# Gecko_IO.net
KiCad netlist of a schematic drawn in Altium Designer
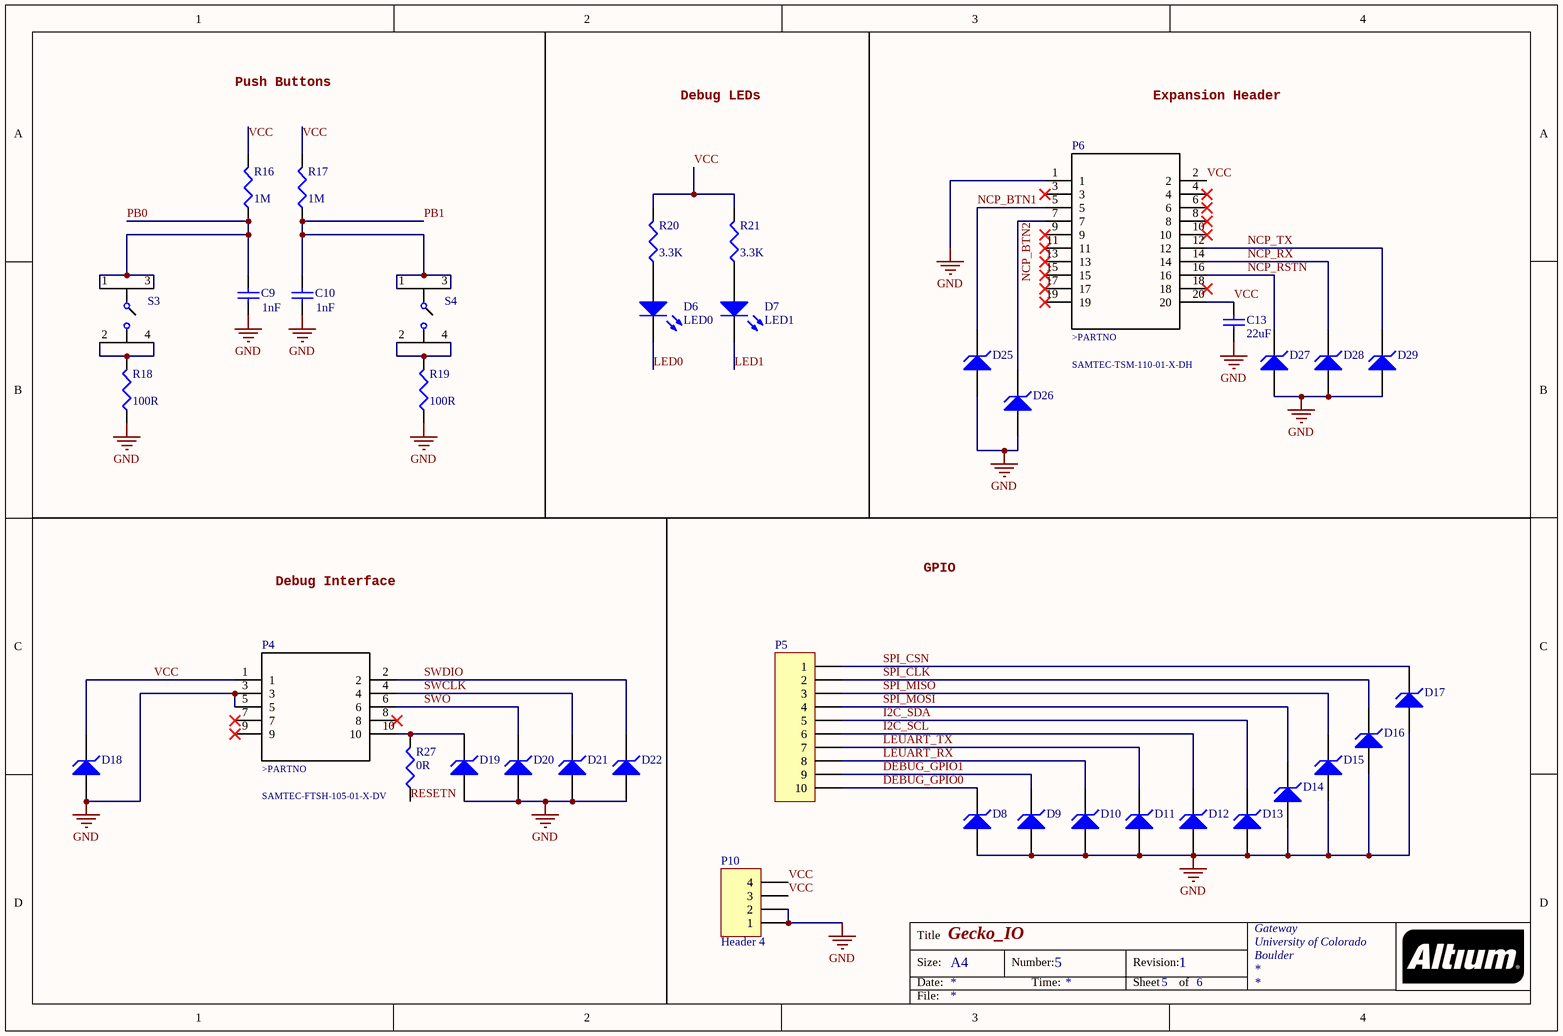
[diagram p0: Gecko_IO.SchDoc]

(export (version "E")
  (design (tool "Eeschema 10.0.6"))
  (components
    (comp (ref "C9")
      (value "1nF")
      (footprint "1608[0603]")
      (description "CAP CER 1000PF 50V X7R 0603")
      (fields
        (field (name "DIGI-KEY PART NUMBER") "478-5006-1-ND")
        (field (name "MANUFACTURER") "AVX Corporation")
        (field (name "PUBLISHER") "Altium Limited")
      )
      (libsource (lib "Miscellaneous Devices") (part "Cap"))
    )
    (comp (ref "C10")
      (value "1nF")
      (footprint "1608[0603]")
      (description "CAP CER 1000PF 50V X7R 0603")
      (fields
        (field (name "DIGI-KEY PART NUMBER") "478-5006-1-ND")
        (field (name "MANUFACTURER") "AVX Corporation")
        (field (name "PUBLISHER") "Altium Limited")
      )
      (libsource (lib "Miscellaneous Devices") (part "Cap"))
    )
    (comp (ref "C13")
      (value "22uF")
      (footprint "1608[0603]")
      (description "CAP CER 22UF 10V X5R 0603")
      (fields
        (field (name "MANUFACTURER") "Samsung Electro-Mechanics")
        (field (name "MANUFACTURER PART NUMBER") "CL10A226MPCNUBE")
        (field (name "PUBLISHER") "Altium Limited")
      )
      (libsource (lib "Miscellaneous Devices") (part "Cap"))
    )
    (comp (ref "D6")
      (value "LED0")
      (footprint "1608[0603]")
      (description "LED GREEN DIFFUSED 0603 SMD")
      (fields
        (field (name "DIGI-KEY PART NUMBER") "475-3118-1-ND")
        (field (name "MANUFACTURER") "OSRAM Opto Semiconductors Inc.")
      )
      (libsource (lib "Miscellaneous Devices") (part "LED2"))
    )
    (comp (ref "D7")
      (value "LED1")
      (footprint "1608[0603]")
      (description "LED GREEN DIFFUSED 0603 SMD")
      (fields
        (field (name "DIGI-KEY PART NUMBER") "475-3118-1-ND")
        (field (name "MANUFACTURER") "OSRAM Opto Semiconductors Inc.")
      )
      (libsource (lib "Miscellaneous Devices") (part "LED2"))
    )
    (comp (ref "D8")
      (value "CZRQR3V3B-HF")
      (footprint "0402")
      (description "DIODE ZENER 3.3V 125MW 0402")
      (fields
        (field (name "DIGI-KEY PART NUMBER") "641-1682-1-ND")
        (field (name "MANUFACTURER") "Comchip Technology")
      )
      (libsource (lib "Miscellaneous Devices") (part "D Zener"))
    )
    (comp (ref "D9")
      (value "CZRQR3V3B-HF")
      (footprint "0402")
      (description "DIODE ZENER 3.3V 125MW 0402")
      (fields
        (field (name "DIGI-KEY PART NUMBER") "641-1682-1-ND")
        (field (name "MANUFACTURER") "Comchip Technology")
      )
      (libsource (lib "Miscellaneous Devices") (part "D Zener"))
    )
    (comp (ref "D10")
      (value "CZRQR3V3B-HF")
      (footprint "0402")
      (description "DIODE ZENER 3.3V 125MW 0402")
      (fields
        (field (name "DIGI-KEY PART NUMBER") "641-1682-1-ND")
        (field (name "MANUFACTURER") "Comchip Technology")
      )
      (libsource (lib "Miscellaneous Devices") (part "D Zener"))
    )
    (comp (ref "D11")
      (value "CZRQR3V3B-HF")
      (footprint "0402")
      (description "DIODE ZENER 3.3V 125MW 0402")
      (fields
        (field (name "DIGI-KEY PART NUMBER") "641-1682-1-ND")
        (field (name "MANUFACTURER") "Comchip Technology")
      )
      (libsource (lib "Miscellaneous Devices") (part "D Zener"))
    )
    (comp (ref "D12")
      (value "CZRQR3V3B-HF")
      (footprint "0402")
      (description "DIODE ZENER 3.3V 125MW 0402")
      (fields
        (field (name "DIGI-KEY PART NUMBER") "641-1682-1-ND")
        (field (name "MANUFACTURER") "Comchip Technology")
      )
      (libsource (lib "Miscellaneous Devices") (part "D Zener"))
    )
    (comp (ref "D13")
      (value "CZRQR3V3B-HF")
      (footprint "0402")
      (description "DIODE ZENER 3.3V 125MW 0402")
      (fields
        (field (name "DIGI-KEY PART NUMBER") "641-1682-1-ND")
        (field (name "MANUFACTURER") "Comchip Technology")
      )
      (libsource (lib "Miscellaneous Devices") (part "D Zener"))
    )
    (comp (ref "D14")
      (value "CZRQR3V3B-HF")
      (footprint "0402")
      (description "DIODE ZENER 3.3V 125MW 0402")
      (fields
        (field (name "DIGI-KEY PART NUMBER") "641-1682-1-ND")
        (field (name "MANUFACTURER") "Comchip Technology")
      )
      (libsource (lib "Miscellaneous Devices") (part "D Zener"))
    )
    (comp (ref "D15")
      (value "CZRQR3V3B-HF")
      (footprint "0402")
      (description "DIODE ZENER 3.3V 125MW 0402")
      (fields
        (field (name "DIGI-KEY PART NUMBER") "641-1682-1-ND")
        (field (name "MANUFACTURER") "Comchip Technology")
      )
      (libsource (lib "Miscellaneous Devices") (part "D Zener"))
    )
    (comp (ref "D16")
      (value "CZRQR3V3B-HF")
      (footprint "0402")
      (description "DIODE ZENER 3.3V 125MW 0402")
      (fields
        (field (name "DIGI-KEY PART NUMBER") "641-1682-1-ND")
        (field (name "MANUFACTURER") "Comchip Technology")
      )
      (libsource (lib "Miscellaneous Devices") (part "D Zener"))
    )
    (comp (ref "D17")
      (value "CZRQR3V3B-HF")
      (footprint "0402")
      (description "DIODE ZENER 3.3V 125MW 0402")
      (fields
        (field (name "DIGI-KEY PART NUMBER") "641-1682-1-ND")
        (field (name "MANUFACTURER") "Comchip Technology")
      )
      (libsource (lib "Miscellaneous Devices") (part "D Zener"))
    )
    (comp (ref "D18")
      (value "CZRQR3V3B-HF")
      (footprint "0402")
      (description "DIODE ZENER 3.3V 125MW 0402")
      (fields
        (field (name "DIGI-KEY PART NUMBER") "641-1682-1-ND")
        (field (name "MANUFACTURER") "Comchip Technology")
      )
      (libsource (lib "Miscellaneous Devices") (part "D Zener"))
    )
    (comp (ref "D19")
      (value "CZRQR3V3B-HF")
      (footprint "0402")
      (description "DIODE ZENER 3.3V 125MW 0402")
      (fields
        (field (name "DIGI-KEY PART NUMBER") "641-1682-1-ND")
        (field (name "MANUFACTURER") "Comchip Technology")
      )
      (libsource (lib "Miscellaneous Devices") (part "D Zener"))
    )
    (comp (ref "D20")
      (value "CZRQR3V3B-HF")
      (footprint "0402")
      (description "DIODE ZENER 3.3V 125MW 0402")
      (fields
        (field (name "DIGI-KEY PART NUMBER") "641-1682-1-ND")
        (field (name "MANUFACTURER") "Comchip Technology")
      )
      (libsource (lib "Miscellaneous Devices") (part "D Zener"))
    )
    (comp (ref "D21")
      (value "CZRQR3V3B-HF")
      (footprint "0402")
      (description "DIODE ZENER 3.3V 125MW 0402")
      (fields
        (field (name "DIGI-KEY PART NUMBER") "641-1682-1-ND")
        (field (name "MANUFACTURER") "Comchip Technology")
      )
      (libsource (lib "Miscellaneous Devices") (part "D Zener"))
    )
    (comp (ref "D22")
      (value "CZRQR3V3B-HF")
      (footprint "0402")
      (description "DIODE ZENER 3.3V 125MW 0402")
      (fields
        (field (name "DIGI-KEY PART NUMBER") "641-1682-1-ND")
        (field (name "MANUFACTURER") "Comchip Technology")
      )
      (libsource (lib "Miscellaneous Devices") (part "D Zener"))
    )
    (comp (ref "D25")
      (value "CZRQR3V3B-HF")
      (footprint "0402")
      (description "DIODE ZENER 3.3V 125MW 0402")
      (fields
        (field (name "DIGI-KEY PART NUMBER") "641-1682-1-ND")
        (field (name "MANUFACTURER") "Comchip Technology")
      )
      (libsource (lib "Miscellaneous Devices") (part "D Zener"))
    )
    (comp (ref "D26")
      (value "CZRQR3V3B-HF")
      (footprint "0402")
      (description "DIODE ZENER 3.3V 125MW 0402")
      (fields
        (field (name "DIGI-KEY PART NUMBER") "641-1682-1-ND")
        (field (name "MANUFACTURER") "Comchip Technology")
      )
      (libsource (lib "Miscellaneous Devices") (part "D Zener"))
    )
    (comp (ref "D27")
      (value "CZRQR3V3B-HF")
      (footprint "0402")
      (description "DIODE ZENER 3.3V 125MW 0402")
      (fields
        (field (name "DIGI-KEY PART NUMBER") "641-1682-1-ND")
        (field (name "MANUFACTURER") "Comchip Technology")
      )
      (libsource (lib "Miscellaneous Devices") (part "D Zener"))
    )
    (comp (ref "D28")
      (value "CZRQR3V3B-HF")
      (footprint "0402")
      (description "DIODE ZENER 3.3V 125MW 0402")
      (fields
        (field (name "DIGI-KEY PART NUMBER") "641-1682-1-ND")
        (field (name "MANUFACTURER") "Comchip Technology")
      )
      (libsource (lib "Miscellaneous Devices") (part "D Zener"))
    )
    (comp (ref "D29")
      (value "CZRQR3V3B-HF")
      (footprint "0402")
      (description "DIODE ZENER 3.3V 125MW 0402")
      (fields
        (field (name "DIGI-KEY PART NUMBER") "641-1682-1-ND")
        (field (name "MANUFACTURER") "Comchip Technology")
      )
      (libsource (lib "Miscellaneous Devices") (part "D Zener"))
    )
    (comp (ref "P4")
      (value "PROG_HDR")
      (footprint "SAMTEC-FTSH-105-01-X-DV")
      (description ".050\" X .050 TERMINAL STRIP")
      (fields
        (field (name "MANUFACTURER") "Samtec")
        (field (name "MANUFACTURER PART NUMBER") "FTSH-105-01-F-DV-K-TR")
      )
      (libsource (lib "Debug_connector") (part "SAMTEC-FTSH-105-01-X-DV"))
    )
    (comp (ref "P5")
      (value "~")
      (footprint "HDR1X10")
      (description "Header, 10-Pin")
      (fields (field (name "PUBLISHER") "Altium Limited"))
      (libsource (lib "Miscellaneous Connectors") (part "Header 10"))
    )
    (comp (ref "P6")
      (value "TSM-110-01-L-DH-A-P-TR")
      (footprint "SAMTEC-TSM-110-01-X-DH")
      (description ".025 SQ. TERMINAL STRIPS")
      (fields
        (field (name "DIGI-KEY PART NUMBER") "SAM14883CT-ND")
        (field (name "MANUFACTURER") "Samtec Inc.")
      )
      (libsource (lib "SAMTEC-TSM-110-01-X-DH") (part "SAMTEC-TSM-110-01-X-DH"))
    )
    (comp (ref "P10")
      (value "Header 4")
      (footprint "HDR1X4")
      (description "Header, 4-Pin")
      (fields (field (name "PUBLISHER") "Altium Limited"))
      (libsource (lib "Miscellaneous Connectors") (part "Header 4"))
    )
    (comp (ref "R16")
      (value "1M")
      (footprint "1608[0603]")
      (description "RES SMD 1M OHM 5% 1/10W 0603")
      (fields
        (field (name "DIGI-KEY PART NUMBER") "1276-5134-1-ND")
        (field (name "MANUFACTURER") "Samsung Electro-Mechanics")
        (field (name "PUBLISHER") "Altium Limited")
      )
      (libsource (lib "Miscellaneous Devices") (part "Res3"))
    )
    (comp (ref "R17")
      (value "1M")
      (footprint "1608[0603]")
      (description "RES SMD 1M OHM 5% 1/10W 0603")
      (fields
        (field (name "DIGI-KEY PART NUMBER") "1276-5134-1-ND")
        (field (name "MANUFACTURER") "Samsung Electro-Mechanics")
        (field (name "PUBLISHER") "Altium Limited")
      )
      (libsource (lib "Miscellaneous Devices") (part "Res3"))
    )
    (comp (ref "R18")
      (value "100R")
      (footprint "1608[0603]")
      (description "RES SMD 100 OHM 5% 1/10W 0603")
      (fields
        (field (name "DIGI-KEY PART NUMBER") "541-4059-1-ND")
        (field (name "MANUFACTURER") "Vishay Dale")
        (field (name "PUBLISHER") "Altium Limited")
      )
      (libsource (lib "Miscellaneous Devices") (part "Res3"))
    )
    (comp (ref "R19")
      (value "100R")
      (footprint "1608[0603]")
      (description "RES SMD 100 OHM 5% 1/10W 0603")
      (fields
        (field (name "DIGI-KEY PART NUMBER") "541-4059-1-ND")
        (field (name "MANUFACTURER") "Vishay Dale")
        (field (name "PUBLISHER") "Altium Limited")
      )
      (libsource (lib "Miscellaneous Devices") (part "Res3"))
    )
    (comp (ref "R20")
      (value "3.3K")
      (footprint "1608[0603]")
      (description "RES SMD 3.3K OHM 5% 1/10W 0603")
      (fields
        (field (name "DIGI-KEY PART NUMBER") "P3.3KGCT-ND")
        (field (name "MANUFACTURER") "Panasonic Electronic Components")
      )
      (libsource (lib "Miscellaneous Devices") (part "Res3"))
    )
    (comp (ref "R21")
      (value "3.3K")
      (footprint "1608[0603]")
      (description "RES SMD 3.3K OHM 5% 1/10W 0603")
      (fields
        (field (name "DIGI-KEY PART NUMBER") "P3.3KGCT-ND")
        (field (name "MANUFACTURER") "Panasonic Electronic Components")
      )
      (libsource (lib "Miscellaneous Devices") (part "Res3"))
    )
    (comp (ref "R27")
      (value "0R")
      (footprint "C1206")
      (description "RES 0 OHM JUMPER 1/8W 0603")
      (fields
        (field (name "DIGI-KEY PART NUMBER") "749-1745-1-ND")
        (field (name "MANUFACTURER") "Vishay Beyschlag")
        (field (name "PUBLISHER") "Altium Limited")
      )
      (libsource (lib "Miscellaneous Devices") (part "Res3"))
    )
    (comp (ref "S3")
      (value "PB0")
      (footprint "430182043816")
      (description "SWITCH TACTILE SPST-NO 0.05A 12V")
      (fields
        (field (name "MANUFACTURER PART NUMBER") "430182043816")
        (field (name "MANUFACTURER") "Wurth Electronics")
      )
      (libsource (lib "430182043816") (part "430182043816"))
    )
    (comp (ref "S4")
      (value "PB1")
      (footprint "430182043816")
      (description "SWITCH TACTILE SPST-NO 0.05A 12V")
      (fields
        (field (name "MANUFACTURER PART NUMBER") "430182043816")
        (field (name "MANUFACTURER") "Wurth Electronics")
      )
      (libsource (lib "430182043816") (part "430182043816"))
    )
  )
  (nets
    (net (code "1") (name "/DEBUG_GPIO0") (class "Default")
      (node (ref "D8") (pin "2") (pinfunction "K_2") (pintype "passive"))
      (node (ref "P5") (pin "10") (pinfunction "10_10") (pintype "passive"))
    )
    (net (code "2") (name "/DEBUG_GPIO1") (class "Default")
      (node (ref "D9") (pin "2") (pinfunction "K_2") (pintype "passive"))
      (node (ref "P5") (pin "9") (pinfunction "9_9") (pintype "passive"))
    )
    (net (code "3") (name "/I2C_SCL") (class "Default")
      (node (ref "D12") (pin "2") (pinfunction "K_2") (pintype "passive"))
      (node (ref "P5") (pin "6") (pinfunction "6_6") (pintype "passive"))
    )
    (net (code "4") (name "/I2C_SDA") (class "Default")
      (node (ref "D13") (pin "2") (pinfunction "K_2") (pintype "passive"))
      (node (ref "P5") (pin "5") (pinfunction "5_5") (pintype "passive"))
    )
    (net (code "5") (name "/LED0") (class "Default")
      (node (ref "D6") (pin "2") (pinfunction "K_2") (pintype "passive"))
    )
    (net (code "6") (name "/LED1") (class "Default")
      (node (ref "D7") (pin "2") (pinfunction "K_2") (pintype "passive"))
    )
    (net (code "7") (name "/LEUART_RX") (class "Default")
      (node (ref "D10") (pin "2") (pinfunction "K_2") (pintype "passive"))
      (node (ref "P5") (pin "8") (pinfunction "8_8") (pintype "passive"))
    )
    (net (code "8") (name "/LEUART_TX") (class "Default")
      (node (ref "D11") (pin "2") (pinfunction "K_2") (pintype "passive"))
      (node (ref "P5") (pin "7") (pinfunction "7_7") (pintype "passive"))
    )
    (net (code "9") (name "/NCP_BTN1") (class "Default")
      (node (ref "D25") (pin "2") (pinfunction "K_2") (pintype "passive"))
      (node (ref "P6") (pin "5") (pinfunction "5_5") (pintype "passive"))
    )
    (net (code "10") (name "/NCP_BTN2") (class "Default")
      (node (ref "D26") (pin "2") (pinfunction "K_2") (pintype "passive"))
      (node (ref "P6") (pin "7") (pinfunction "7_7") (pintype "passive"))
    )
    (net (code "11") (name "/NCP_RSTN") (class "Default")
      (node (ref "D27") (pin "2") (pinfunction "K_2") (pintype "passive"))
      (node (ref "P6") (pin "16") (pinfunction "16_16") (pintype "passive"))
    )
    (net (code "12") (name "/NCP_RX") (class "Default")
      (node (ref "D28") (pin "2") (pinfunction "K_2") (pintype "passive"))
      (node (ref "P6") (pin "14") (pinfunction "14_14") (pintype "passive"))
    )
    (net (code "13") (name "/NCP_TX") (class "Default")
      (node (ref "D29") (pin "2") (pinfunction "K_2") (pintype "passive"))
      (node (ref "P6") (pin "12") (pinfunction "12_12") (pintype "passive"))
    )
    (net (code "14") (name "/PB0") (class "Default")
      (node (ref "C9") (pin "2") (pinfunction "2_2") (pintype "passive"))
      (node (ref "R16") (pin "1") (pinfunction "1_1") (pintype "passive"))
      (node (ref "S3") (pin "1") (pinfunction "1_1") (pintype "passive"))
      (node (ref "S3") (pin "3") (pinfunction "3_3") (pintype "passive"))
    )
    (net (code "15") (name "/PB1") (class "Default")
      (node (ref "C10") (pin "2") (pinfunction "2_2") (pintype "passive"))
      (node (ref "R17") (pin "1") (pinfunction "1_1") (pintype "passive"))
      (node (ref "S4") (pin "1") (pinfunction "1_1") (pintype "passive"))
      (node (ref "S4") (pin "3") (pinfunction "3_3") (pintype "passive"))
    )
    (net (code "16") (name "/RESETN") (class "Default")
      (node (ref "R27") (pin "1") (pinfunction "1_1") (pintype "passive"))
    )
    (net (code "17") (name "/SPI_CLK") (class "Default")
      (node (ref "D16") (pin "2") (pinfunction "K_2") (pintype "passive"))
      (node (ref "P5") (pin "2") (pinfunction "2_2") (pintype "passive"))
    )
    (net (code "18") (name "/SPI_CSN") (class "Default")
      (node (ref "D17") (pin "2") (pinfunction "K_2") (pintype "passive"))
      (node (ref "P5") (pin "1") (pinfunction "1_1") (pintype "passive"))
    )
    (net (code "19") (name "/SPI_MISO") (class "Default")
      (node (ref "D15") (pin "2") (pinfunction "K_2") (pintype "passive"))
      (node (ref "P5") (pin "3") (pinfunction "3_3") (pintype "passive"))
    )
    (net (code "20") (name "/SPI_MOSI") (class "Default")
      (node (ref "D14") (pin "2") (pinfunction "K_2") (pintype "passive"))
      (node (ref "P5") (pin "4") (pinfunction "4_4") (pintype "passive"))
    )
    (net (code "21") (name "/SWCLK") (class "Default")
      (node (ref "D21") (pin "2") (pinfunction "K_2") (pintype "passive"))
      (node (ref "P4") (pin "4") (pinfunction "4_4") (pintype "passive"))
    )
    (net (code "22") (name "/SWDIO") (class "Default")
      (node (ref "D22") (pin "2") (pinfunction "K_2") (pintype "passive"))
      (node (ref "P4") (pin "2") (pinfunction "2_2") (pintype "passive"))
    )
    (net (code "23") (name "/SWO") (class "Default")
      (node (ref "D20") (pin "2") (pinfunction "K_2") (pintype "passive"))
      (node (ref "P4") (pin "6") (pinfunction "6_6") (pintype "passive"))
    )
    (net (code "24") (name "/VCC") (class "Default")
      (node (ref "C13") (pin "1") (pinfunction "1_1") (pintype "passive"))
      (node (ref "D18") (pin "2") (pinfunction "K_2") (pintype "passive"))
      (node (ref "P10") (pin "3") (pinfunction "3_3") (pintype "passive"))
      (node (ref "P10") (pin "4") (pinfunction "4_4") (pintype "passive"))
      (node (ref "P4") (pin "1") (pinfunction "1_1") (pintype "passive"))
      (node (ref "P6") (pin "2") (pinfunction "2_2") (pintype "passive"))
      (node (ref "P6") (pin "20") (pinfunction "20_20") (pintype "passive"))
      (node (ref "R16") (pin "2") (pinfunction "2_2") (pintype "passive"))
      (node (ref "R17") (pin "2") (pinfunction "2_2") (pintype "passive"))
      (node (ref "R20") (pin "2") (pinfunction "2_2") (pintype "passive"))
      (node (ref "R21") (pin "2") (pinfunction "2_2") (pintype "passive"))
    )
    (net (code "25") (name "GND") (class "Default")
      (node (ref "C10") (pin "1") (pinfunction "1_1") (pintype "passive"))
      (node (ref "C13") (pin "2") (pinfunction "2_2") (pintype "passive"))
      (node (ref "C9") (pin "1") (pinfunction "1_1") (pintype "passive"))
      (node (ref "D10") (pin "1") (pinfunction "A_1") (pintype "passive"))
      (node (ref "D11") (pin "1") (pinfunction "A_1") (pintype "passive"))
      (node (ref "D12") (pin "1") (pinfunction "A_1") (pintype "passive"))
      (node (ref "D13") (pin "1") (pinfunction "A_1") (pintype "passive"))
      (node (ref "D14") (pin "1") (pinfunction "A_1") (pintype "passive"))
      (node (ref "D15") (pin "1") (pinfunction "A_1") (pintype "passive"))
      (node (ref "D16") (pin "1") (pinfunction "A_1") (pintype "passive"))
      (node (ref "D17") (pin "1") (pinfunction "A_1") (pintype "passive"))
      (node (ref "D18") (pin "1") (pinfunction "A_1") (pintype "passive"))
      (node (ref "D19") (pin "1") (pinfunction "A_1") (pintype "passive"))
      (node (ref "D20") (pin "1") (pinfunction "A_1") (pintype "passive"))
      (node (ref "D21") (pin "1") (pinfunction "A_1") (pintype "passive"))
      (node (ref "D22") (pin "1") (pinfunction "A_1") (pintype "passive"))
      (node (ref "D25") (pin "1") (pinfunction "A_1") (pintype "passive"))
      (node (ref "D26") (pin "1") (pinfunction "A_1") (pintype "passive"))
      (node (ref "D27") (pin "1") (pinfunction "A_1") (pintype "passive"))
      (node (ref "D28") (pin "1") (pinfunction "A_1") (pintype "passive"))
      (node (ref "D29") (pin "1") (pinfunction "A_1") (pintype "passive"))
      (node (ref "D8") (pin "1") (pinfunction "A_1") (pintype "passive"))
      (node (ref "D9") (pin "1") (pinfunction "A_1") (pintype "passive"))
      (node (ref "P10") (pin "1") (pinfunction "1_1") (pintype "passive"))
      (node (ref "P10") (pin "2") (pinfunction "2_2") (pintype "passive"))
      (node (ref "P4") (pin "3") (pinfunction "3_3") (pintype "passive"))
      (node (ref "P4") (pin "5") (pinfunction "5_5") (pintype "passive"))
      (node (ref "P6") (pin "1") (pinfunction "1_1") (pintype "passive"))
      (node (ref "R18") (pin "1") (pinfunction "1_1") (pintype "passive"))
      (node (ref "R19") (pin "1") (pinfunction "1_1") (pintype "passive"))
    )
    (net (code "26") (name "Net-(D6-A)") (class "Default")
      (node (ref "D6") (pin "1") (pinfunction "A_1") (pintype "passive"))
      (node (ref "R20") (pin "1") (pinfunction "1_1") (pintype "passive"))
    )
    (net (code "27") (name "Net-(D7-A)") (class "Default")
      (node (ref "D7") (pin "1") (pinfunction "A_1") (pintype "passive"))
      (node (ref "R21") (pin "1") (pinfunction "1_1") (pintype "passive"))
    )
    (net (code "28") (name "Net-(D19-K)") (class "Default")
      (node (ref "D19") (pin "2") (pinfunction "K_2") (pintype "passive"))
      (node (ref "P4") (pin "10") (pinfunction "10_10") (pintype "passive"))
      (node (ref "R27") (pin "2") (pinfunction "2_2") (pintype "passive"))
    )
    (net (code "29") (name "Net-(R18-Pad2)") (class "Default")
      (node (ref "R18") (pin "2") (pinfunction "2_2") (pintype "passive"))
      (node (ref "S3") (pin "2") (pinfunction "2_2") (pintype "passive"))
      (node (ref "S3") (pin "4") (pinfunction "4_4") (pintype "passive"))
    )
    (net (code "30") (name "Net-(R19-Pad2)") (class "Default")
      (node (ref "R19") (pin "2") (pinfunction "2_2") (pintype "passive"))
      (node (ref "S4") (pin "2") (pinfunction "2_2") (pintype "passive"))
      (node (ref "S4") (pin "4") (pinfunction "4_4") (pintype "passive"))
    )
    (net (code "31") (name "unconnected-(P4-Pad7)") (class "Default")
      (node (ref "P4") (pin "7") (pinfunction "7_7") (pintype "passive+no_connect"))
    )
    (net (code "32") (name "unconnected-(P4-Pad8)") (class "Default")
      (node (ref "P4") (pin "8") (pinfunction "8_8") (pintype "passive+no_connect"))
    )
    (net (code "33") (name "unconnected-(P4-Pad9)") (class "Default")
      (node (ref "P4") (pin "9") (pinfunction "9_9") (pintype "passive+no_connect"))
    )
    (net (code "34") (name "unconnected-(P6-Pad3)") (class "Default")
      (node (ref "P6") (pin "3") (pinfunction "3_3") (pintype "passive+no_connect"))
    )
    (net (code "35") (name "unconnected-(P6-Pad4)") (class "Default")
      (node (ref "P6") (pin "4") (pinfunction "4_4") (pintype "passive+no_connect"))
    )
    (net (code "36") (name "unconnected-(P6-Pad6)") (class "Default")
      (node (ref "P6") (pin "6") (pinfunction "6_6") (pintype "passive+no_connect"))
    )
    (net (code "37") (name "unconnected-(P6-Pad8)") (class "Default")
      (node (ref "P6") (pin "8") (pinfunction "8_8") (pintype "passive+no_connect"))
    )
    (net (code "38") (name "unconnected-(P6-Pad9)") (class "Default")
      (node (ref "P6") (pin "9") (pinfunction "9_9") (pintype "passive+no_connect"))
    )
    (net (code "39") (name "unconnected-(P6-Pad10)") (class "Default")
      (node (ref "P6") (pin "10") (pinfunction "10_10") (pintype "passive+no_connect"))
    )
    (net (code "40") (name "unconnected-(P6-Pad11)") (class "Default")
      (node (ref "P6") (pin "11") (pinfunction "11_11") (pintype "passive+no_connect"))
    )
    (net (code "41") (name "unconnected-(P6-Pad13)") (class "Default")
      (node (ref "P6") (pin "13") (pinfunction "13_13") (pintype "passive+no_connect"))
    )
    (net (code "42") (name "unconnected-(P6-Pad15)") (class "Default")
      (node (ref "P6") (pin "15") (pinfunction "15_15") (pintype "passive+no_connect"))
    )
    (net (code "43") (name "unconnected-(P6-Pad17)") (class "Default")
      (node (ref "P6") (pin "17") (pinfunction "17_17") (pintype "passive+no_connect"))
    )
    (net (code "44") (name "unconnected-(P6-Pad18)") (class "Default")
      (node (ref "P6") (pin "18") (pinfunction "18_18") (pintype "passive+no_connect"))
    )
    (net (code "45") (name "unconnected-(P6-Pad19)") (class "Default")
      (node (ref "P6") (pin "19") (pinfunction "19_19") (pintype "passive+no_connect"))
    )
  )
)
